# Raincenter_APP-ARM0_0_1.net
KiCad netlist of a schematic drawn in EAGLE
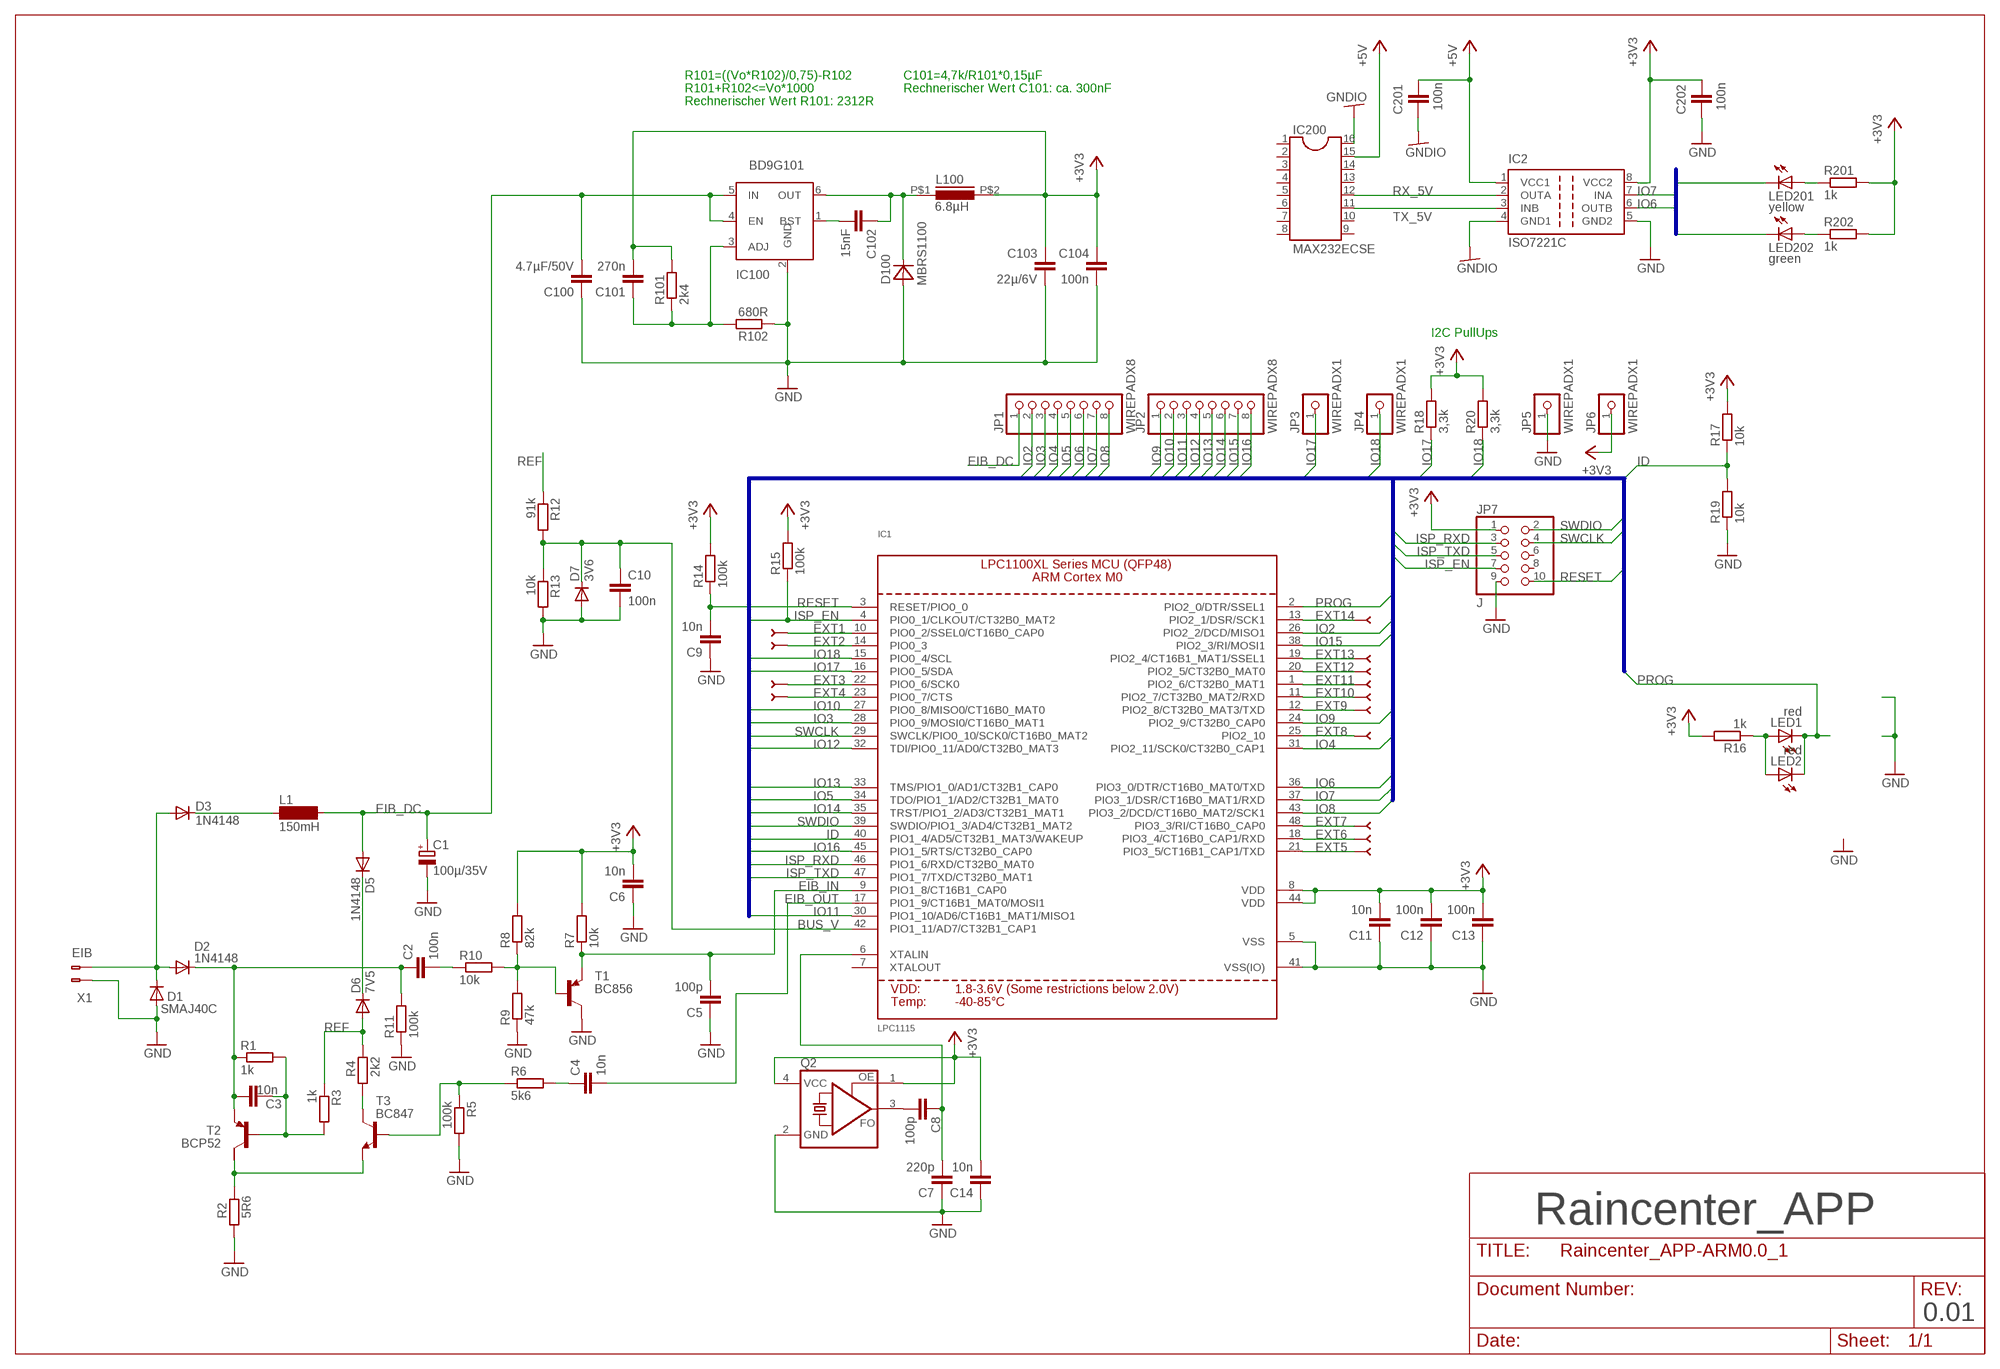
[diagram p0: schematic, sheet 1]

(export (version "E")
  (design (tool "Eeschema 10.0.6"))
  (components
    (comp (ref "C1")
      (value "100µ/35V")
      (footprint "eagle-import:SANYO-OSCON_SMD_C6")
      (libsource (lib "eagle-import") (part "CPOL-EUSANYO_SMD_C6"))
    )
    (comp (ref "C2")
      (value "100n")
      (footprint "eagle-import:C1206")
      (libsource (lib "eagle-import") (part "C-EUC1206"))
    )
    (comp (ref "C3")
      (value "10n")
      (footprint "eagle-import:C1206")
      (libsource (lib "eagle-import") (part "C-EUC1206"))
    )
    (comp (ref "C4")
      (value "10n")
      (footprint "eagle-import:C1206")
      (libsource (lib "eagle-import") (part "C-EUC1206"))
    )
    (comp (ref "C5")
      (value "100p")
      (footprint "eagle-import:C1206")
      (libsource (lib "eagle-import") (part "C-EUC1206"))
    )
    (comp (ref "C6")
      (value "10n")
      (footprint "eagle-import:C1206")
      (libsource (lib "eagle-import") (part "C-EUC1206"))
    )
    (comp (ref "C7")
      (value "220p")
      (footprint "eagle-import:C1206")
      (libsource (lib "eagle-import") (part "C-EUC1206"))
    )
    (comp (ref "C8")
      (value "100p")
      (footprint "eagle-import:C1206")
      (libsource (lib "eagle-import") (part "C-EUC1206"))
    )
    (comp (ref "C9")
      (value "10n")
      (footprint "eagle-import:C1206")
      (libsource (lib "eagle-import") (part "C-EUC1206"))
    )
    (comp (ref "C10")
      (value "100n")
      (footprint "eagle-import:C1206")
      (libsource (lib "eagle-import") (part "C-EUC1206"))
    )
    (comp (ref "C11")
      (value "10n")
      (footprint "eagle-import:C1206")
      (libsource (lib "eagle-import") (part "C-EUC1206"))
    )
    (comp (ref "C12")
      (value "100n")
      (footprint "eagle-import:C1206")
      (libsource (lib "eagle-import") (part "C-EUC1206"))
    )
    (comp (ref "C13")
      (value "100n")
      (footprint "eagle-import:C1206")
      (libsource (lib "eagle-import") (part "C-EUC1206"))
    )
    (comp (ref "C14")
      (value "10n")
      (footprint "eagle-import:C1206")
      (libsource (lib "eagle-import") (part "C-EUC1206"))
    )
    (comp (ref "C100")
      (value "4.7µF/50V")
      (footprint "eagle-import:C1206")
      (libsource (lib "eagle-import") (part "C-EUC1206"))
    )
    (comp (ref "C101")
      (value "270n")
      (footprint "eagle-import:C1206")
      (libsource (lib "eagle-import") (part "C-EUC1206"))
    )
    (comp (ref "C102")
      (value "15nF")
      (footprint "eagle-import:C1206")
      (libsource (lib "eagle-import") (part "C-EUC1206"))
    )
    (comp (ref "C103")
      (value "22µ/6V")
      (footprint "eagle-import:C1206")
      (libsource (lib "eagle-import") (part "C-EUC1206"))
    )
    (comp (ref "C104")
      (value "100n")
      (footprint "eagle-import:C1206")
      (libsource (lib "eagle-import") (part "C-EUC1206"))
    )
    (comp (ref "C201")
      (value "100n")
      (footprint "eagle-import:C1206")
      (libsource (lib "eagle-import") (part "C-EUC1206"))
    )
    (comp (ref "C202")
      (value "100n")
      (footprint "eagle-import:C1206")
      (libsource (lib "eagle-import") (part "C-EUC1206"))
    )
    (comp (ref "D1")
      (value "SMAJ40C")
      (footprint "eagle-import:SMB")
      (libsource (lib "eagle-import") (part "D-SMB"))
    )
    (comp (ref "D2")
      (value "1N4148")
      (footprint "eagle-import:MINIMELF")
      (libsource (lib "eagle-import") (part "DIODE-MINIMELF"))
    )
    (comp (ref "D3")
      (value "1N4148")
      (footprint "eagle-import:MINIMELF")
      (libsource (lib "eagle-import") (part "DIODE-MINIMELF"))
    )
    (comp (ref "D5")
      (value "1N4148")
      (footprint "eagle-import:MINIMELF")
      (libsource (lib "eagle-import") (part "DIODE-MINIMELF"))
    )
    (comp (ref "D6")
      (value "7V5")
      (footprint "eagle-import:MINIMELF")
      (libsource (lib "eagle-import") (part "DIODE-MINIMELF"))
    )
    (comp (ref "D7")
      (value "3V6")
      (footprint "eagle-import:MINIMELF")
      (libsource (lib "eagle-import") (part "DIODE-MINIMELF"))
    )
    (comp (ref "D100")
      (value "MBRS1100")
      (footprint "eagle-import:SMA")
      (libsource (lib "eagle-import") (part "MBRA340T3"))
    )
    (comp (ref "IC1")
      (value "LPC1115")
      (footprint "eagle-import:LQFP48")
      (libsource (lib "eagle-import") (part "LPC1113/4/5_QFP48_XLSERIES"))
    )
    (comp (ref "IC2")
      (value "ISO7221C")
      (footprint "eagle-import:SO-08")
      (fields (field (name "MPN") "ISO7221CD"))
      (libsource (lib "eagle-import") (part "ISO7221C"))
    )
    (comp (ref "IC100")
      (value "BD9G101")
      (footprint "eagle-import:SOT23-6")
      (libsource (lib "eagle-import") (part "BD9G101GBD9G101G-SOT23-6"))
    )
    (comp (ref "IC200")
      (value "MAX232ECSE")
      (footprint "eagle-import:SOCKET-16")
      (libsource (lib "eagle-import") (part "DIL16S"))
    )
    (comp (ref "JP1")
      (value "WIREPADX8")
      (footprint "eagle-import:SMD1,27X2,54X8")
      (libsource (lib "eagle-import") (part "WIREPADX8"))
    )
    (comp (ref "JP2")
      (value "WIREPADX8")
      (footprint "eagle-import:SMD1,27X2,54X8")
      (libsource (lib "eagle-import") (part "WIREPADX8"))
    )
    (comp (ref "JP3")
      (value "WIREPADX1")
      (footprint "eagle-import:SMD1,27X2,54")
      (libsource (lib "eagle-import") (part "WIREPADX1"))
    )
    (comp (ref "JP4")
      (value "WIREPADX1")
      (footprint "eagle-import:SMD1,27X2,54")
      (libsource (lib "eagle-import") (part "WIREPADX1"))
    )
    (comp (ref "JP5")
      (value "WIREPADX1")
      (footprint "eagle-import:SMD1,27X2,54")
      (libsource (lib "eagle-import") (part "WIREPADX1"))
    )
    (comp (ref "JP6")
      (value "WIREPADX1")
      (footprint "eagle-import:SMD1,27X2,54")
      (libsource (lib "eagle-import") (part "WIREPADX1"))
    )
    (comp (ref "JP7")
      (value "J")
      (footprint "eagle-import:2X05M")
      (libsource (lib "eagle-import") (part "PINHD-2X05_2.00"))
    )
    (comp (ref "L1")
      (value "150mH")
      (footprint "eagle-import:SD12_1000")
      (libsource (lib "eagle-import") (part "SD12-1000"))
    )
    (comp (ref "L100")
      (value "6.8µH")
      (footprint "eagle-import:PIS2812")
      (libsource (lib "eagle-import") (part "IND_FASTRON_1616FPS"))
    )
    (comp (ref "LED1")
      (value "red")
      (footprint "eagle-import:CHIPLED_1206")
      (libsource (lib "eagle-import") (part "LEDCHIPLED_1206"))
    )
    (comp (ref "LED2")
      (value "red")
      (footprint "eagle-import:LED3MM")
      (libsource (lib "eagle-import") (part "LED3MM"))
    )
    (comp (ref "LED201")
      (value "yellow")
      (footprint "eagle-import:CHIPLED_1206")
      (libsource (lib "eagle-import") (part "LEDCHIPLED_1206"))
    )
    (comp (ref "LED202")
      (value "green")
      (footprint "eagle-import:CHIPLED_1206")
      (libsource (lib "eagle-import") (part "LEDCHIPLED_1206"))
    )
    (comp (ref "P1")
      (value "PAD")
      (footprint "eagle-import:PAD")
      (libsource (lib "eagle-import") (part "PAD"))
    )
    (comp (ref "P2")
      (value "PAD")
      (footprint "eagle-import:PAD")
      (libsource (lib "eagle-import") (part "PAD"))
    )
    (comp (ref "P3")
      (value "PAD")
      (footprint "eagle-import:PAD")
      (libsource (lib "eagle-import") (part "PAD"))
    )
    (comp (ref "P4")
      (value "PAD")
      (footprint "eagle-import:PAD")
      (libsource (lib "eagle-import") (part "PAD"))
    )
    (comp (ref "P5")
      (value "PAD")
      (footprint "eagle-import:PAD")
      (libsource (lib "eagle-import") (part "PAD"))
    )
    (comp (ref "P6")
      (value "PAD")
      (footprint "eagle-import:PAD")
      (libsource (lib "eagle-import") (part "PAD"))
    )
    (comp (ref "P7")
      (value "PAD")
      (footprint "eagle-import:PAD")
      (libsource (lib "eagle-import") (part "PAD"))
    )
    (comp (ref "P8")
      (value "PAD")
      (footprint "eagle-import:PAD")
      (libsource (lib "eagle-import") (part "PAD"))
    )
    (comp (ref "P9")
      (value "PAD")
      (footprint "eagle-import:PAD")
      (libsource (lib "eagle-import") (part "PAD"))
    )
    (comp (ref "P10")
      (value "PAD")
      (footprint "eagle-import:PAD")
      (libsource (lib "eagle-import") (part "PAD"))
    )
    (comp (ref "P11")
      (value "PAD")
      (footprint "eagle-import:PAD")
      (libsource (lib "eagle-import") (part "PAD"))
    )
    (comp (ref "P12")
      (value "PAD")
      (footprint "eagle-import:PAD")
      (libsource (lib "eagle-import") (part "PAD"))
    )
    (comp (ref "P13")
      (value "PAD")
      (footprint "eagle-import:PAD")
      (libsource (lib "eagle-import") (part "PAD"))
    )
    (comp (ref "P14")
      (value "PAD")
      (footprint "eagle-import:PAD")
      (libsource (lib "eagle-import") (part "PAD"))
    )
    (comp (ref "Q2")
      (value "ASFL")
      (footprint "eagle-import:ASF")
      (libsource (lib "eagle-import") (part "ASFL"))
    )
    (comp (ref "R1")
      (value "1k")
      (footprint "eagle-import:R1206")
      (libsource (lib "eagle-import") (part "R-EU_R1206"))
    )
    (comp (ref "R2")
      (value "5R6")
      (footprint "eagle-import:R1206")
      (libsource (lib "eagle-import") (part "R-EU_R1206"))
    )
    (comp (ref "R3")
      (value "1k")
      (footprint "eagle-import:R1206")
      (libsource (lib "eagle-import") (part "R-EU_R1206"))
    )
    (comp (ref "R4")
      (value "2k2")
      (footprint "eagle-import:R1206")
      (libsource (lib "eagle-import") (part "R-EU_R1206"))
    )
    (comp (ref "R5")
      (value "100k")
      (footprint "eagle-import:R1206")
      (libsource (lib "eagle-import") (part "R-EU_R1206"))
    )
    (comp (ref "R6")
      (value "5k6")
      (footprint "eagle-import:R1206")
      (libsource (lib "eagle-import") (part "R-EU_R1206"))
    )
    (comp (ref "R7")
      (value "10k")
      (footprint "eagle-import:R1206")
      (libsource (lib "eagle-import") (part "R-EU_R1206"))
    )
    (comp (ref "R8")
      (value "82k")
      (footprint "eagle-import:R1206")
      (libsource (lib "eagle-import") (part "R-EU_R1206"))
    )
    (comp (ref "R9")
      (value "47k")
      (footprint "eagle-import:R1206")
      (libsource (lib "eagle-import") (part "R-EU_R1206"))
    )
    (comp (ref "R10")
      (value "10k")
      (footprint "eagle-import:R1206")
      (libsource (lib "eagle-import") (part "R-EU_R1206"))
    )
    (comp (ref "R11")
      (value "100k")
      (footprint "eagle-import:R1206")
      (libsource (lib "eagle-import") (part "R-EU_R1206"))
    )
    (comp (ref "R12")
      (value "91k")
      (footprint "eagle-import:R1206")
      (libsource (lib "eagle-import") (part "R-EU_R1206"))
    )
    (comp (ref "R13")
      (value "10k")
      (footprint "eagle-import:R1206")
      (libsource (lib "eagle-import") (part "R-EU_R1206"))
    )
    (comp (ref "R14")
      (value "100k")
      (footprint "eagle-import:R1206")
      (libsource (lib "eagle-import") (part "R-EU_R1206"))
    )
    (comp (ref "R15")
      (value "100k")
      (footprint "eagle-import:R1206")
      (libsource (lib "eagle-import") (part "R-EU_R1206"))
    )
    (comp (ref "R16")
      (value "1k")
      (footprint "eagle-import:R1206")
      (libsource (lib "eagle-import") (part "R-EU_R1206"))
    )
    (comp (ref "R17")
      (value "10k")
      (footprint "eagle-import:R1206")
      (libsource (lib "eagle-import") (part "R-EU_R1206"))
    )
    (comp (ref "R18")
      (value "3,3k")
      (footprint "eagle-import:R1206")
      (libsource (lib "eagle-import") (part "R-EU_R1206"))
    )
    (comp (ref "R19")
      (value "10k")
      (footprint "eagle-import:R1206")
      (libsource (lib "eagle-import") (part "R-EU_R1206"))
    )
    (comp (ref "R20")
      (value "3,3k")
      (footprint "eagle-import:R1206")
      (libsource (lib "eagle-import") (part "R-EU_R1206"))
    )
    (comp (ref "R101")
      (value "2k4")
      (footprint "eagle-import:R1206")
      (libsource (lib "eagle-import") (part "R-EU_R1206"))
    )
    (comp (ref "R102")
      (value "680R")
      (footprint "eagle-import:R1206")
      (libsource (lib "eagle-import") (part "R-EU_R1206"))
    )
    (comp (ref "R201")
      (value "1k")
      (footprint "eagle-import:R1206")
      (libsource (lib "eagle-import") (part "R-EU_R1206"))
    )
    (comp (ref "R202")
      (value "1k")
      (footprint "eagle-import:R1206")
      (libsource (lib "eagle-import") (part "R-EU_R1206"))
    )
    (comp (ref "T1")
      (value "BC856")
      (footprint "eagle-import:SOT23-BEC")
      (libsource (lib "eagle-import") (part "BC856SMDB"))
    )
    (comp (ref "T2")
      (value "BCP52")
      (footprint "eagle-import:SOT223")
      (libsource (lib "eagle-import") (part "FZT753SMD"))
    )
    (comp (ref "T3")
      (value "BC847")
      (footprint "eagle-import:SOT23")
      (libsource (lib "eagle-import") (part "BC847"))
    )
    (comp (ref "X1")
      (value "EIB")
      (footprint "eagle-import:BUSKLEMME243-724")
      (libsource (lib "eagle-import") (part "EIB"))
    )
  )
  (nets
    (net (code "1") (name "+3V3") (class "Default")
      (node (ref "C101") (pin "2") (pinfunction "2_2") (pintype "passive"))
      (node (ref "C103") (pin "1") (pinfunction "1_1") (pintype "passive"))
      (node (ref "C104") (pin "1") (pinfunction "1_1") (pintype "passive"))
      (node (ref "C11") (pin "2") (pinfunction "2_2") (pintype "passive"))
      (node (ref "C12") (pin "2") (pinfunction "2_2") (pintype "passive"))
      (node (ref "C13") (pin "2") (pinfunction "2_2") (pintype "passive"))
      (node (ref "C14") (pin "2") (pinfunction "2_2") (pintype "passive"))
      (node (ref "C202") (pin "1") (pinfunction "1_1") (pintype "passive"))
      (node (ref "C6") (pin "2") (pinfunction "2_2") (pintype "passive"))
      (node (ref "IC1") (pin "44") (pinfunction "VDD_44") (pintype "power_in"))
      (node (ref "IC1") (pin "8") (pinfunction "VDD_8") (pintype "power_in"))
      (node (ref "IC2") (pin "8") (pinfunction "VCC2_8") (pintype "power_in"))
      (node (ref "JP6") (pin "1") (pinfunction "1_1") (pintype "passive"))
      (node (ref "JP7") (pin "1") (pinfunction "1_1") (pintype "passive"))
      (node (ref "L100") (pin "P$2") (pinfunction "2_P$2") (pintype "passive"))
      (node (ref "Q2") (pin "1") (pinfunction "OE_1") (pintype "input"))
      (node (ref "Q2") (pin "4") (pinfunction "VCC_4") (pintype "power_in"))
      (node (ref "R101") (pin "2") (pinfunction "2_2") (pintype "passive"))
      (node (ref "R14") (pin "2") (pinfunction "2_2") (pintype "passive"))
      (node (ref "R15") (pin "2") (pinfunction "2_2") (pintype "passive"))
      (node (ref "R16") (pin "2") (pinfunction "2_2") (pintype "passive"))
      (node (ref "R17") (pin "2") (pinfunction "2_2") (pintype "passive"))
      (node (ref "R18") (pin "2") (pinfunction "2_2") (pintype "passive"))
      (node (ref "R20") (pin "2") (pinfunction "2_2") (pintype "passive"))
      (node (ref "R201") (pin "2") (pinfunction "2_2") (pintype "passive"))
      (node (ref "R202") (pin "2") (pinfunction "2_2") (pintype "passive"))
      (node (ref "R7") (pin "2") (pinfunction "2_2") (pintype "passive"))
      (node (ref "R8") (pin "2") (pinfunction "2_2") (pintype "passive"))
    )
    (net (code "2") (name "+5V") (class "Default")
      (node (ref "C201") (pin "1") (pinfunction "1_1") (pintype "passive"))
      (node (ref "IC2") (pin "1") (pinfunction "VCC1_1") (pintype "power_in"))
      (node (ref "IC200") (pin "15") (pinfunction "15_15") (pintype "passive"))
    )
    (net (code "3") (name "/BUS_V") (class "Default")
      (node (ref "C10") (pin "2") (pinfunction "2_2") (pintype "passive"))
      (node (ref "D7") (pin "C") (pinfunction "C_C") (pintype "passive"))
      (node (ref "IC1") (pin "42") (pinfunction "PIO1_11/AD7/CT32B1_CAP1_42") (pintype "bidirectional"))
      (node (ref "R12") (pin "2") (pinfunction "2_2") (pintype "passive"))
      (node (ref "R13") (pin "1") (pinfunction "1_1") (pintype "passive"))
    )
    (net (code "4") (name "/EIB_DC") (class "Default")
      (node (ref "C1") (pin "+") (pinfunction "+_+") (pintype "passive"))
      (node (ref "C100") (pin "2") (pinfunction "2_2") (pintype "passive"))
      (node (ref "D5") (pin "A") (pinfunction "A_A") (pintype "passive"))
      (node (ref "IC100") (pin "4") (pinfunction "EN_4") (pintype "input"))
      (node (ref "IC100") (pin "5") (pinfunction "IN_5") (pintype "input"))
      (node (ref "JP1") (pin "1") (pinfunction "1_1") (pintype "passive"))
      (node (ref "L1") (pin "2") (pinfunction "2_2") (pintype "passive"))
    )
    (net (code "5") (name "/EIB_IN") (class "Default")
      (node (ref "C5") (pin "2") (pinfunction "2_2") (pintype "passive"))
      (node (ref "IC1") (pin "9") (pinfunction "PIO1_8/CT16B1_CAP0_9") (pintype "bidirectional"))
      (node (ref "R7") (pin "1") (pinfunction "1_1") (pintype "passive"))
      (node (ref "T1") (pin "E") (pinfunction "E_E") (pintype "passive"))
    )
    (net (code "6") (name "/EIB_OUT") (class "Default")
      (node (ref "C4") (pin "2") (pinfunction "2_2") (pintype "passive"))
      (node (ref "IC1") (pin "17") (pinfunction "PIO1_9/CT16B1_MAT0/MOSI1_17") (pintype "bidirectional"))
    )
    (net (code "7") (name "/EXT1") (class "Default")
      (node (ref "IC1") (pin "10") (pinfunction "PIO0_2/SSEL0/CT16B0_CAP0_10") (pintype "bidirectional"))
      (node (ref "P1") (pin "1") (pinfunction "1_1") (pintype "bidirectional"))
    )
    (net (code "8") (name "/EXT2") (class "Default")
      (node (ref "IC1") (pin "14") (pinfunction "PIO0_3_14") (pintype "bidirectional"))
      (node (ref "P2") (pin "1") (pinfunction "1_1") (pintype "bidirectional"))
    )
    (net (code "9") (name "/EXT3") (class "Default")
      (node (ref "IC1") (pin "22") (pinfunction "PIO0_6/SCK0_22") (pintype "bidirectional"))
      (node (ref "P13") (pin "1") (pinfunction "1_1") (pintype "bidirectional"))
    )
    (net (code "10") (name "/EXT4") (class "Default")
      (node (ref "IC1") (pin "23") (pinfunction "PIO0_7/CTS_23") (pintype "bidirectional"))
      (node (ref "P14") (pin "1") (pinfunction "1_1") (pintype "bidirectional"))
    )
    (net (code "11") (name "/EXT5") (class "Default")
      (node (ref "IC1") (pin "21") (pinfunction "PIO3_5/CT16B1_CAP1/TXD_21") (pintype "bidirectional"))
      (node (ref "P12") (pin "1") (pinfunction "1_1") (pintype "bidirectional"))
    )
    (net (code "12") (name "/EXT6") (class "Default")
      (node (ref "IC1") (pin "18") (pinfunction "PIO3_4/CT16B0_CAP1/RXD_18") (pintype "bidirectional"))
      (node (ref "P11") (pin "1") (pinfunction "1_1") (pintype "bidirectional"))
    )
    (net (code "13") (name "/EXT7") (class "Default")
      (node (ref "IC1") (pin "48") (pinfunction "PIO3_3/RI/CT16B0_CAP0_48") (pintype "bidirectional"))
      (node (ref "P10") (pin "1") (pinfunction "1_1") (pintype "bidirectional"))
    )
    (net (code "14") (name "/EXT8") (class "Default")
      (node (ref "IC1") (pin "25") (pinfunction "PIO2_10_25") (pintype "bidirectional"))
      (node (ref "P6") (pin "1") (pinfunction "1_1") (pintype "bidirectional"))
    )
    (net (code "15") (name "/EXT9") (class "Default")
      (node (ref "IC1") (pin "12") (pinfunction "PIO2_8/CT32B0_MAT3/TXD_12") (pintype "bidirectional"))
      (node (ref "P4") (pin "1") (pinfunction "1_1") (pintype "bidirectional"))
    )
    (net (code "16") (name "/EXT10") (class "Default")
      (node (ref "IC1") (pin "11") (pinfunction "PIO2_7/CT32B0_MAT2/RXD_11") (pintype "bidirectional"))
      (node (ref "P5") (pin "1") (pinfunction "1_1") (pintype "bidirectional"))
    )
    (net (code "17") (name "/EXT11") (class "Default")
      (node (ref "IC1") (pin "1") (pinfunction "PIO2_6/CT32B0_MAT1_1") (pintype "bidirectional"))
      (node (ref "P9") (pin "1") (pinfunction "1_1") (pintype "bidirectional"))
    )
    (net (code "18") (name "/EXT12") (class "Default")
      (node (ref "IC1") (pin "20") (pinfunction "PIO2_5/CT32B0_MAT0_20") (pintype "bidirectional"))
      (node (ref "P8") (pin "1") (pinfunction "1_1") (pintype "bidirectional"))
    )
    (net (code "19") (name "/EXT13") (class "Default")
      (node (ref "IC1") (pin "19") (pinfunction "PIO2_4/CT16B1_MAT1/SSEL1_19") (pintype "bidirectional"))
      (node (ref "P7") (pin "1") (pinfunction "1_1") (pintype "bidirectional"))
    )
    (net (code "20") (name "/EXT14") (class "Default")
      (node (ref "IC1") (pin "13") (pinfunction "PIO2_1/DSR/SCK1_13") (pintype "bidirectional"))
      (node (ref "P3") (pin "1") (pinfunction "1_1") (pintype "bidirectional"))
    )
    (net (code "21") (name "/ID") (class "Default")
      (node (ref "IC1") (pin "40") (pinfunction "PIO1_4/AD5/CT32B1_MAT3/WAKEUP_40") (pintype "bidirectional"))
      (node (ref "R17") (pin "1") (pinfunction "1_1") (pintype "passive"))
      (node (ref "R19") (pin "2") (pinfunction "2_2") (pintype "passive"))
    )
    (net (code "22") (name "/IO1") (class "Default")
      (node (ref "IC1") (pin "2") (pinfunction "PIO2_0/DTR/SSEL1_2") (pintype "bidirectional"))
      (node (ref "LED1") (pin "C") (pinfunction "C_C") (pintype "passive"))
      (node (ref "LED2") (pin "K") (pinfunction "C_K") (pintype "passive"))
    )
    (net (code "23") (name "/IO2") (class "Default")
      (node (ref "IC1") (pin "26") (pinfunction "PIO2_2/DCD/MISO1_26") (pintype "bidirectional"))
      (node (ref "JP1") (pin "2") (pinfunction "2_2") (pintype "passive"))
      (node (ref "LED201") (pin "C") (pinfunction "C_C") (pintype "passive"))
    )
    (net (code "24") (name "/IO3") (class "Default")
      (node (ref "IC1") (pin "28") (pinfunction "PIO0_9/MOSI0/CT16B0_MAT1_28") (pintype "bidirectional"))
      (node (ref "JP1") (pin "3") (pinfunction "3_3") (pintype "passive"))
      (node (ref "LED202") (pin "C") (pinfunction "C_C") (pintype "passive"))
    )
    (net (code "25") (name "/IO4") (class "Default")
      (node (ref "IC1") (pin "31") (pinfunction "PIO2_11/SCK0/CT32B0_CAP1_31") (pintype "bidirectional"))
      (node (ref "JP1") (pin "4") (pinfunction "4_4") (pintype "passive"))
    )
    (net (code "26") (name "/IO5") (class "Default")
      (node (ref "IC1") (pin "34") (pinfunction "TDO/PIO1_1/AD2/CT32B1_MAT0_34") (pintype "bidirectional"))
      (node (ref "JP1") (pin "5") (pinfunction "5_5") (pintype "passive"))
    )
    (net (code "27") (name "/IO6") (class "Default")
      (node (ref "IC1") (pin "36") (pinfunction "PIO3_0/DTR/CT16B0_MAT0/TXD_36") (pintype "bidirectional"))
      (node (ref "IC2") (pin "6") (pinfunction "OUTB_6") (pintype "output"))
      (node (ref "JP1") (pin "6") (pinfunction "6_6") (pintype "passive"))
    )
    (net (code "28") (name "/IO7") (class "Default")
      (node (ref "IC1") (pin "37") (pinfunction "PIO3_1/DSR/CT16B0_MAT1/RXD_37") (pintype "bidirectional"))
      (node (ref "IC2") (pin "7") (pinfunction "INA_7") (pintype "input"))
      (node (ref "JP1") (pin "7") (pinfunction "7_7") (pintype "passive"))
    )
    (net (code "29") (name "/IO8") (class "Default")
      (node (ref "IC1") (pin "43") (pinfunction "PIO3_2/DCD/CT16B0_MAT2/SCK1_43") (pintype "bidirectional"))
      (node (ref "JP1") (pin "8") (pinfunction "8_8") (pintype "passive"))
    )
    (net (code "30") (name "/IO9") (class "Default")
      (node (ref "IC1") (pin "24") (pinfunction "PIO2_9/CT32B0_CAP0_24") (pintype "bidirectional"))
      (node (ref "JP2") (pin "1") (pinfunction "1_1") (pintype "passive"))
    )
    (net (code "31") (name "/IO10") (class "Default")
      (node (ref "IC1") (pin "27") (pinfunction "PIO0_8/MISO0/CT16B0_MAT0_27") (pintype "bidirectional"))
      (node (ref "JP2") (pin "2") (pinfunction "2_2") (pintype "passive"))
    )
    (net (code "32") (name "/IO11") (class "Default")
      (node (ref "IC1") (pin "30") (pinfunction "PIO1_10/AD6/CT16B1_MAT1/MISO1_30") (pintype "bidirectional"))
      (node (ref "JP2") (pin "3") (pinfunction "3_3") (pintype "passive"))
    )
    (net (code "33") (name "/IO12") (class "Default")
      (node (ref "IC1") (pin "32") (pinfunction "TDI/PIO0_11/AD0/CT32B0_MAT3_32") (pintype "bidirectional"))
      (node (ref "JP2") (pin "4") (pinfunction "4_4") (pintype "passive"))
    )
    (net (code "34") (name "/IO13") (class "Default")
      (node (ref "IC1") (pin "33") (pinfunction "TMS/PIO1_0/AD1/CT32B1_CAP0_33") (pintype "bidirectional"))
      (node (ref "JP2") (pin "5") (pinfunction "5_5") (pintype "passive"))
    )
    (net (code "35") (name "/IO14") (class "Default")
      (node (ref "IC1") (pin "35") (pinfunction "TRST/PIO1_2/AD3/CT32B1_MAT1_35") (pintype "bidirectional"))
      (node (ref "JP2") (pin "6") (pinfunction "6_6") (pintype "passive"))
    )
    (net (code "36") (name "/IO15") (class "Default")
      (node (ref "IC1") (pin "38") (pinfunction "PIO2_3/RI/MOSI1_38") (pintype "bidirectional"))
      (node (ref "JP2") (pin "7") (pinfunction "7_7") (pintype "passive"))
    )
    (net (code "37") (name "/IO16") (class "Default")
      (node (ref "IC1") (pin "45") (pinfunction "PIO1_5/RTS/CT32B0_CAP0_45") (pintype "bidirectional"))
      (node (ref "JP2") (pin "8") (pinfunction "8_8") (pintype "passive"))
    )
    (net (code "38") (name "/IO17") (class "Default")
      (node (ref "IC1") (pin "16") (pinfunction "PIO0_5/SDA_16") (pintype "bidirectional"))
      (node (ref "JP3") (pin "1") (pinfunction "1_1") (pintype "passive"))
      (node (ref "R18") (pin "1") (pinfunction "1_1") (pintype "passive"))
    )
    (net (code "39") (name "/IO18") (class "Default")
      (node (ref "IC1") (pin "15") (pinfunction "PIO0_4/SCL_15") (pintype "bidirectional"))
      (node (ref "JP4") (pin "1") (pinfunction "1_1") (pintype "passive"))
      (node (ref "R20") (pin "1") (pinfunction "1_1") (pintype "passive"))
    )
    (net (code "40") (name "/ISP_EN") (class "Default")
      (node (ref "IC1") (pin "4") (pinfunction "PIO0_1/CLKOUT/CT32B0_MAT2_4") (pintype "bidirectional"))
      (node (ref "JP7") (pin "7") (pinfunction "7_7") (pintype "passive"))
      (node (ref "R15") (pin "1") (pinfunction "1_1") (pintype "passive"))
    )
    (net (code "41") (name "/ISP_RXD") (class "Default")
      (node (ref "IC1") (pin "46") (pinfunction "PIO1_6/RXD/CT32B0_MAT0_46") (pintype "bidirectional"))
      (node (ref "JP7") (pin "3") (pinfunction "3_3") (pintype "passive"))
    )
    (net (code "42") (name "/ISP_TXD") (class "Default")
      (node (ref "IC1") (pin "47") (pinfunction "PIO1_7/TXD/CT32B0_MAT1_47") (pintype "bidirectional"))
      (node (ref "JP7") (pin "5") (pinfunction "5_5") (pintype "passive"))
    )
    (net (code "43") (name "/REF") (class "Default")
      (node (ref "D6") (pin "A") (pinfunction "A_A") (pintype "passive"))
      (node (ref "R12") (pin "1") (pinfunction "1_1") (pintype "passive"))
      (node (ref "R3") (pin "1") (pinfunction "1_1") (pintype "passive"))
      (node (ref "R4") (pin "2") (pinfunction "2_2") (pintype "passive"))
    )
    (net (code "44") (name "/RESET") (class "Default")
      (node (ref "C9") (pin "2") (pinfunction "2_2") (pintype "passive"))
      (node (ref "IC1") (pin "3") (pinfunction "RESET/PIO0_0_3") (pintype "bidirectional"))
      (node (ref "JP7") (pin "10") (pinfunction "10_10") (pintype "passive"))
      (node (ref "R14") (pin "1") (pinfunction "1_1") (pintype "passive"))
    )
    (net (code "45") (name "/RX_5V") (class "Default")
      (node (ref "IC2") (pin "2") (pinfunction "OUTA_2") (pintype "output"))
      (node (ref "IC200") (pin "12") (pinfunction "12_12") (pintype "passive"))
    )
    (net (code "46") (name "/SWCLK") (class "Default")
      (node (ref "IC1") (pin "29") (pinfunction "SWCLK/PIO0_10/SCK0/CT16B0_MAT2_29") (pintype "bidirectional"))
      (node (ref "JP7") (pin "4") (pinfunction "4_4") (pintype "passive"))
    )
    (net (code "47") (name "/SWDIO") (class "Default")
      (node (ref "IC1") (pin "39") (pinfunction "SWDIO/PIO1_3/AD4/CT32B1_MAT2_39") (pintype "bidirectional"))
      (node (ref "JP7") (pin "2") (pinfunction "2_2") (pintype "passive"))
    )
    (net (code "48") (name "/TX_5V") (class "Default")
      (node (ref "IC2") (pin "3") (pinfunction "INB_3") (pintype "input"))
      (node (ref "IC200") (pin "11") (pinfunction "11_11") (pintype "passive"))
    )
    (net (code "50") (name "GND") (class "Default")
      (node (ref "C1") (pin "-") (pinfunction "-_-") (pintype "passive"))
      (node (ref "C10") (pin "1") (pinfunction "1_1") (pintype "passive"))
      (node (ref "C100") (pin "1") (pinfunction "1_1") (pintype "passive"))
      (node (ref "C103") (pin "2") (pinfunction "2_2") (pintype "passive"))
      (node (ref "C104") (pin "2") (pinfunction "2_2") (pintype "passive"))
      (node (ref "C11") (pin "1") (pinfunction "1_1") (pintype "passive"))
      (node (ref "C12") (pin "1") (pinfunction "1_1") (pintype "passive"))
      (node (ref "C13") (pin "1") (pinfunction "1_1") (pintype "passive"))
      (node (ref "C14") (pin "1") (pinfunction "1_1") (pintype "passive"))
      (node (ref "C202") (pin "2") (pinfunction "2_2") (pintype "passive"))
      (node (ref "C5") (pin "1") (pinfunction "1_1") (pintype "passive"))
      (node (ref "C6") (pin "1") (pinfunction "1_1") (pintype "passive"))
      (node (ref "C7") (pin "1") (pinfunction "1_1") (pintype "passive"))
      (node (ref "C9") (pin "1") (pinfunction "1_1") (pintype "passive"))
      (node (ref "D1") (pin "2") (pinfunction "A_2") (pintype "passive"))
      (node (ref "D100") (pin "A") (pinfunction "A_A") (pintype "passive"))
      (node (ref "D7") (pin "A") (pinfunction "A_A") (pintype "passive"))
      (node (ref "IC1") (pin "41") (pinfunction "VSS(IO)_41") (pintype "power_in"))
      (node (ref "IC1") (pin "5") (pinfunction "VSS_5") (pintype "power_in"))
      (node (ref "IC100") (pin "2") (pinfunction "GND_2") (pintype "power_in"))
      (node (ref "IC2") (pin "5") (pinfunction "GND2_5") (pintype "power_in"))
      (node (ref "JP5") (pin "1") (pinfunction "1_1") (pintype "passive"))
      (node (ref "JP7") (pin "9") (pinfunction "9_9") (pintype "passive"))
      (node (ref "Q2") (pin "2") (pinfunction "GND_2") (pintype "power_in"))
      (node (ref "R102") (pin "1") (pinfunction "1_1") (pintype "passive"))
      (node (ref "R11") (pin "1") (pinfunction "1_1") (pintype "passive"))
      (node (ref "R13") (pin "2") (pinfunction "2_2") (pintype "passive"))
      (node (ref "R19") (pin "1") (pinfunction "1_1") (pintype "passive"))
      (node (ref "R2") (pin "1") (pinfunction "1_1") (pintype "passive"))
      (node (ref "R5") (pin "2") (pinfunction "2_2") (pintype "passive"))
      (node (ref "R9") (pin "1") (pinfunction "1_1") (pintype "passive"))
      (node (ref "T1") (pin "C") (pinfunction "C_C") (pintype "passive"))
      (node (ref "X1") (pin "1") (pinfunction "B-1_1") (pintype "passive"))
    )
    (net (code "51") (name "GNDIO") (class "Default")
      (node (ref "C201") (pin "2") (pinfunction "2_2") (pintype "passive"))
      (node (ref "IC2") (pin "4") (pinfunction "GND1_4") (pintype "power_in"))
      (node (ref "IC200") (pin "16") (pinfunction "16_16") (pintype "passive"))
    )
    (net (code "52") (name "Net-(C2-Pad2)") (class "Default")
      (node (ref "C2") (pin "2") (pinfunction "2_2") (pintype "passive"))
      (node (ref "R10") (pin "1") (pinfunction "1_1") (pintype "passive"))
    )
    (net (code "53") (name "Net-(C4-Pad1)") (class "Default")
      (node (ref "C4") (pin "1") (pinfunction "1_1") (pintype "passive"))
      (node (ref "R6") (pin "2") (pinfunction "2_2") (pintype "passive"))
    )
    (net (code "54") (name "Net-(D1-C)") (class "Default")
      (node (ref "D1") (pin "1") (pinfunction "C_1") (pintype "passive"))
      (node (ref "D2") (pin "A") (pinfunction "A_A") (pintype "passive"))
      (node (ref "D3") (pin "A") (pinfunction "A_A") (pintype "passive"))
      (node (ref "X1") (pin "2") (pinfunction "B-2_2") (pintype "passive"))
    )
    (net (code "55") (name "Net-(D3-PadC)") (class "Default")
      (node (ref "D3") (pin "C") (pinfunction "C_C") (pintype "passive"))
      (node (ref "L1") (pin "1") (pinfunction "1_1") (pintype "passive"))
    )
    (net (code "56") (name "Net-(D5-PadC)") (class "Default")
      (node (ref "D5") (pin "C") (pinfunction "C_C") (pintype "passive"))
      (node (ref "D6") (pin "C") (pinfunction "C_C") (pintype "passive"))
    )
    (net (code "57") (name "Net-(IC1-XTALIN)") (class "Default")
      (node (ref "C7") (pin "2") (pinfunction "2_2") (pintype "passive"))
      (node (ref "C8") (pin "1") (pinfunction "1_1") (pintype "passive"))
      (node (ref "IC1") (pin "6") (pinfunction "XTALIN_6") (pintype "input"))
    )
    (net (code "58") (name "Net-(IC100-ADJ)") (class "Default")
      (node (ref "C101") (pin "1") (pinfunction "1_1") (pintype "passive"))
      (node (ref "IC100") (pin "3") (pinfunction "ADJ_3") (pintype "passive"))
      (node (ref "R101") (pin "1") (pinfunction "1_1") (pintype "passive"))
      (node (ref "R102") (pin "2") (pinfunction "2_2") (pintype "passive"))
    )
    (net (code "59") (name "Net-(IC100-BST)") (class "Default")
      (node (ref "C102") (pin "2") (pinfunction "2_2") (pintype "passive"))
      (node (ref "IC100") (pin "1") (pinfunction "BST_1") (pintype "output"))
    )
    (net (code "60") (name "Net-(IC100-OUT)") (class "Default")
      (node (ref "C102") (pin "1") (pinfunction "1_1") (pintype "passive"))
      (node (ref "D100") (pin "C") (pinfunction "C_C") (pintype "passive"))
      (node (ref "IC100") (pin "6") (pinfunction "OUT_6") (pintype "output"))
      (node (ref "L100") (pin "P$1") (pinfunction "1_P$1") (pintype "passive"))
    )
    (net (code "61") (name "Net-(LED1-PadA)") (class "Default")
      (node (ref "LED1") (pin "A") (pinfunction "A_A") (pintype "passive"))
      (node (ref "LED2") (pin "A") (pinfunction "A_A") (pintype "passive"))
      (node (ref "R16") (pin "1") (pinfunction "1_1") (pintype "passive"))
    )
    (net (code "62") (name "Net-(LED201-PadA)") (class "Default")
      (node (ref "LED201") (pin "A") (pinfunction "A_A") (pintype "passive"))
      (node (ref "R201") (pin "1") (pinfunction "1_1") (pintype "passive"))
    )
    (net (code "63") (name "Net-(LED202-PadA)") (class "Default")
      (node (ref "LED202") (pin "A") (pinfunction "A_A") (pintype "passive"))
      (node (ref "R202") (pin "1") (pinfunction "1_1") (pintype "passive"))
    )
    (net (code "64") (name "Net-(Q2-FO)") (class "Default")
      (node (ref "C8") (pin "2") (pinfunction "2_2") (pintype "passive"))
      (node (ref "Q2") (pin "3") (pinfunction "FO_3") (pintype "output"))
    )
    (net (code "65") (name "Net-(R10-Pad2)") (class "Default")
      (node (ref "R10") (pin "2") (pinfunction "2_2") (pintype "passive"))
      (node (ref "R8") (pin "1") (pinfunction "1_1") (pintype "passive"))
      (node (ref "R9") (pin "2") (pinfunction "2_2") (pintype "passive"))
      (node (ref "T1") (pin "B") (pinfunction "B_B") (pintype "passive"))
    )
    (net (code "66") (name "Net-(T2-B)") (class "Default")
      (node (ref "C3") (pin "2") (pinfunction "2_2") (pintype "passive"))
      (node (ref "R1") (pin "2") (pinfunction "2_2") (pintype "passive"))
      (node (ref "R3") (pin "2") (pinfunction "2_2") (pintype "passive"))
      (node (ref "T2") (pin "1") (pinfunction "B_1") (pintype "passive"))
    )
    (net (code "67") (name "Net-(T2-C)") (class "Default")
      (node (ref "R2") (pin "2") (pinfunction "2_2") (pintype "passive"))
      (node (ref "T2") (pin "2") (pinfunction "C_2") (pintype "passive"))
      (node (ref "T3") (pin "2") (pinfunction "E_2") (pintype "passive"))
    )
    (net (code "68") (name "Net-(T2-E)") (class "Default")
      (node (ref "C2") (pin "1") (pinfunction "1_1") (pintype "passive"))
      (node (ref "C3") (pin "1") (pinfunction "1_1") (pintype "passive"))
      (node (ref "D2") (pin "C") (pinfunction "C_C") (pintype "passive"))
      (node (ref "R1") (pin "1") (pinfunction "1_1") (pintype "passive"))
      (node (ref "R11") (pin "2") (pinfunction "2_2") (pintype "passive"))
      (node (ref "T2") (pin "3") (pinfunction "E_3") (pintype "passive"))
    )
    (net (code "69") (name "Net-(T3-B)") (class "Default")
      (node (ref "R5") (pin "1") (pinfunction "1_1") (pintype "passive"))
      (node (ref "R6") (pin "1") (pinfunction "1_1") (pintype "passive"))
      (node (ref "T3") (pin "1") (pinfunction "B_1") (pintype "passive"))
    )
    (net (code "70") (name "Net-(T3-C)") (class "Default")
      (node (ref "R4") (pin "1") (pinfunction "1_1") (pintype "passive"))
      (node (ref "T3") (pin "3") (pinfunction "C_3") (pintype "passive"))
    )
    (net (code "71") (name "unconnected-(IC1-XTALOUT-Pad7)") (class "Default")
      (node (ref "IC1") (pin "7") (pinfunction "XTALOUT_7") (pintype "output"))
    )
    (net (code "72") (name "unconnected-(IC200-Pad1)") (class "Default")
      (node (ref "IC200") (pin "1") (pinfunction "1_1") (pintype "passive"))
    )
    (net (code "73") (name "unconnected-(IC200-Pad2)") (class "Default")
      (node (ref "IC200") (pin "2") (pinfunction "2_2") (pintype "passive"))
    )
    (net (code "74") (name "unconnected-(IC200-Pad3)") (class "Default")
      (node (ref "IC200") (pin "3") (pinfunction "3_3") (pintype "passive"))
    )
    (net (code "75") (name "unconnected-(IC200-Pad4)") (class "Default")
      (node (ref "IC200") (pin "4") (pinfunction "4_4") (pintype "passive"))
    )
    (net (code "76") (name "unconnected-(IC200-Pad5)") (class "Default")
      (node (ref "IC200") (pin "5") (pinfunction "5_5") (pintype "passive"))
    )
    (net (code "77") (name "unconnected-(IC200-Pad6)") (class "Default")
      (node (ref "IC200") (pin "6") (pinfunction "6_6") (pintype "passive"))
    )
    (net (code "78") (name "unconnected-(IC200-Pad7)") (class "Default")
      (node (ref "IC200") (pin "7") (pinfunction "7_7") (pintype "passive"))
    )
    (net (code "79") (name "unconnected-(IC200-Pad8)") (class "Default")
      (node (ref "IC200") (pin "8") (pinfunction "8_8") (pintype "passive"))
    )
    (net (code "80") (name "unconnected-(IC200-Pad9)") (class "Default")
      (node (ref "IC200") (pin "9") (pinfunction "9_9") (pintype "passive"))
    )
    (net (code "81") (name "unconnected-(IC200-Pad10)") (class "Default")
      (node (ref "IC200") (pin "10") (pinfunction "10_10") (pintype "passive"))
    )
    (net (code "82") (name "unconnected-(IC200-Pad13)") (class "Default")
      (node (ref "IC200") (pin "13") (pinfunction "13_13") (pintype "passive"))
    )
    (net (code "83") (name "unconnected-(IC200-Pad14)") (class "Default")
      (node (ref "IC200") (pin "14") (pinfunction "14_14") (pintype "passive"))
    )
    (net (code "84") (name "unconnected-(JP7-Pad6)") (class "Default")
      (node (ref "JP7") (pin "6") (pinfunction "6_6") (pintype "passive"))
    )
    (net (code "85") (name "unconnected-(JP7-Pad8)") (class "Default")
      (node (ref "JP7") (pin "8") (pinfunction "8_8") (pintype "passive"))
    )
    (net (code "86") (name "unconnected-(T2-C{slash}-Pad4)") (class "Default")
      (node (ref "T2") (pin "4") (pinfunction "C/_4") (pintype "passive"))
    )
  )
)
